# SensorTile_CR2032_V01.net
KiCad netlist of a schematic drawn in EAGLE
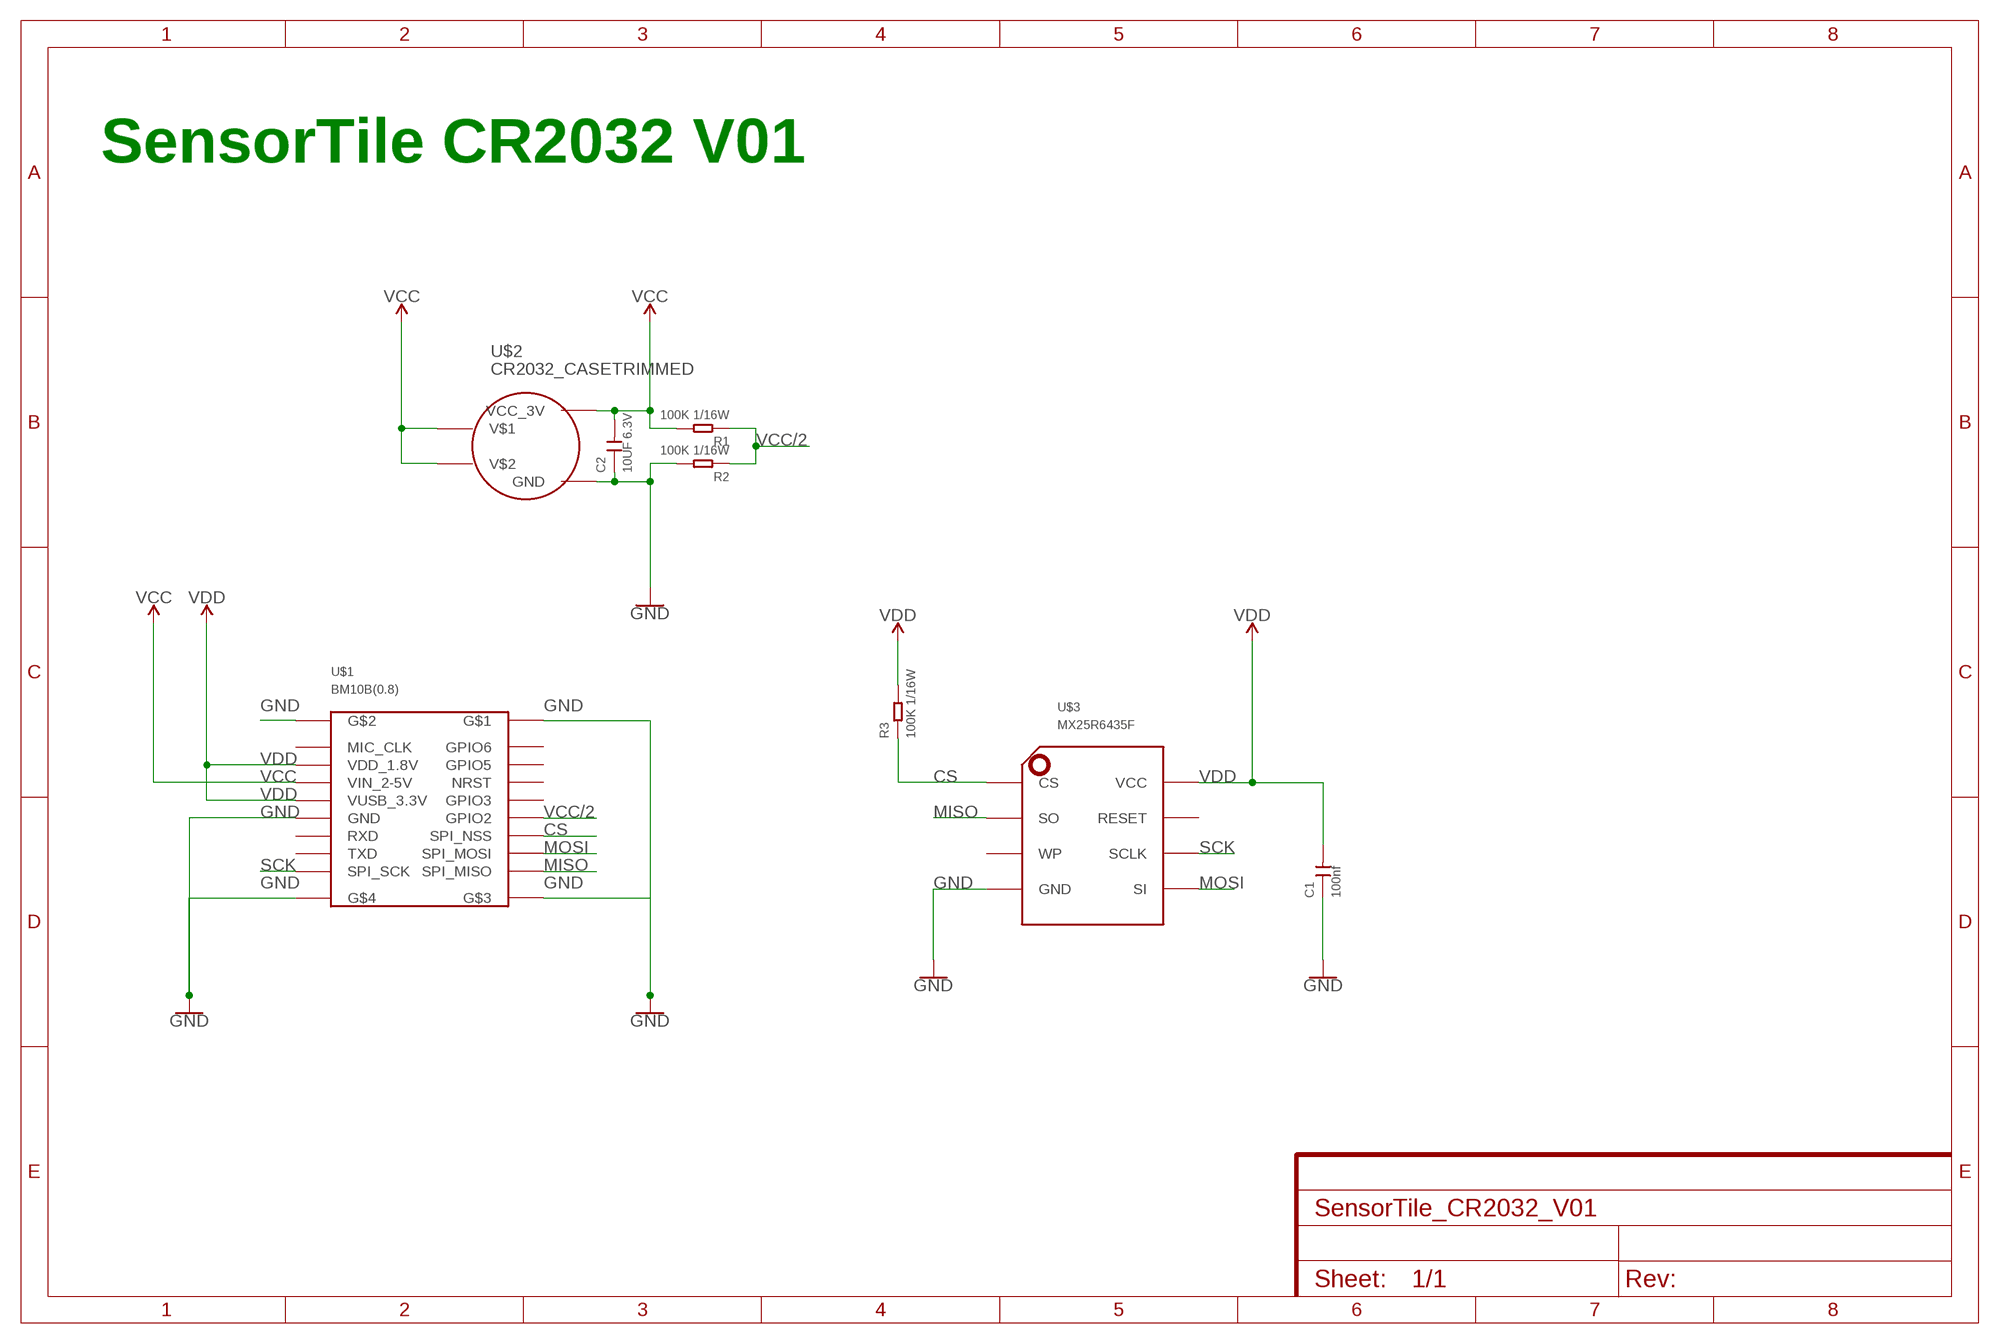
[diagram p0: schematic, sheet 1]

(export (version "E")
  (design (tool "Eeschema 10.0.6"))
  (components
    (comp (ref "C1")
      (value "100nf")
      (footprint "eagle-import:C0402")
      (fields (field (name "MPN") "CC0402KRX7R8BB104"))
      (libsource (lib "eagle-import") (part "CERAMIC-100NF-25V-10%-X7R(0402)"))
    )
    (comp (ref "C2")
      (value "10UF 6.3V")
      (footprint "eagle-import:C0603")
      (fields (field (name "MPN") "CC0603MRX5R5BB106"))
      (libsource (lib "eagle-import") (part "CERAMIC-10UF-6.3V-20%-X5R(0603)"))
    )
    (comp (ref "R1")
      (value "100K 1/16W")
      (footprint "eagle-import:R0402")
      (fields (field (name "MPN") "RC0402JR-07100KL"))
      (libsource (lib "eagle-import") (part "SMD-RES-100K-5%-1/16W(0402)"))
    )
    (comp (ref "R2")
      (value "100K 1/16W")
      (footprint "eagle-import:R0402")
      (fields (field (name "MPN") "RC0402JR-07100KL"))
      (libsource (lib "eagle-import") (part "SMD-RES-100K-5%-1/16W(0402)"))
    )
    (comp (ref "R3")
      (value "100K 1/16W")
      (footprint "eagle-import:R0402")
      (fields (field (name "MPN") "RC0402FR-0710KL"))
      (libsource (lib "eagle-import") (part "SMD-RES-10K-1%-1/16W(0402)"))
    )
    (comp (ref "U$1")
      (value "BM10B(0.8)")
      (footprint "eagle-import:BM10B(0.8)-16DP-0.4V(51)")
      (libsource (lib "eagle-import") (part "BM10B(0.8)-16DP-0.4V(51)"))
    )
    (comp (ref "U$2")
      (value "CR2032_CASETRIMMED")
      (footprint "eagle-import:CR2032_CASE_TRIMMED")
      (libsource (lib "eagle-import") (part "CR2032_CASETRIMMED"))
    )
    (comp (ref "U$3")
      (value "MX25R6435F")
      (footprint "eagle-import:8-USON_MX25R6435F")
      (libsource (lib "eagle-import") (part "MX25R6435F"))
    )
  )
  (nets
    (net (code "1") (name "/CS") (class "Default")
      (node (ref "R3") (pin "1") (pinfunction "1_1") (pintype "passive"))
      (node (ref "U$1") (pin "SPI_NSS") (pinfunction "SPI_NSS_SPI_NSS") (pintype "bidirectional"))
      (node (ref "U$3") (pin "CS$1") (pinfunction "CS_CS$1") (pintype "bidirectional"))
    )
    (net (code "2") (name "/MISO") (class "Default")
      (node (ref "U$1") (pin "SPI_MISO") (pinfunction "SPI_MISO_SPI_MISO") (pintype "bidirectional"))
      (node (ref "U$3") (pin "SO$2") (pinfunction "SO_SO$2") (pintype "bidirectional"))
    )
    (net (code "3") (name "/MOSI") (class "Default")
      (node (ref "U$1") (pin "SPI_MOSI") (pinfunction "SPI_MOSI_SPI_MOSI") (pintype "bidirectional"))
      (node (ref "U$3") (pin "SI$5") (pinfunction "SI_SI$5") (pintype "bidirectional"))
    )
    (net (code "4") (name "/SCK") (class "Default")
      (node (ref "U$1") (pin "SPI_SCK") (pinfunction "SPI_SCK_SPI_SCK") (pintype "bidirectional"))
      (node (ref "U$3") (pin "SCLK$6") (pinfunction "SCLK_SCLK$6") (pintype "bidirectional"))
    )
    (net (code "5") (name "/VCC{slash}2") (class "Default")
      (node (ref "R1") (pin "1") (pinfunction "1_1") (pintype "passive"))
      (node (ref "R2") (pin "1") (pinfunction "1_1") (pintype "passive"))
      (node (ref "U$1") (pin "GPIO2") (pinfunction "GPIO2_GPIO2") (pintype "bidirectional"))
    )
    (net (code "6") (name "GND") (class "Default")
      (node (ref "C1") (pin "1") (pinfunction "1_1") (pintype "passive"))
      (node (ref "C2") (pin "1") (pinfunction "1_1") (pintype "passive"))
      (node (ref "R2") (pin "2") (pinfunction "2_2") (pintype "passive"))
      (node (ref "U$1") (pin "G$1") (pinfunction "G$1_G$1") (pintype "bidirectional"))
      (node (ref "U$1") (pin "G$2") (pinfunction "G$2_G$2") (pintype "bidirectional"))
      (node (ref "U$1") (pin "G$3") (pinfunction "G$3_G$3") (pintype "bidirectional"))
      (node (ref "U$1") (pin "G$4") (pinfunction "G$4_G$4") (pintype "bidirectional"))
      (node (ref "U$1") (pin "GND$1") (pinfunction "GND_GND$1") (pintype "bidirectional"))
      (node (ref "U$2") (pin "GND") (pinfunction "GND_GND") (pintype "bidirectional"))
      (node (ref "U$3") (pin "GND$4") (pinfunction "GND_GND$4") (pintype "bidirectional"))
    )
    (net (code "7") (name "VCC") (class "Default")
      (node (ref "C2") (pin "2") (pinfunction "2_2") (pintype "passive"))
      (node (ref "R1") (pin "2") (pinfunction "2_2") (pintype "passive"))
      (node (ref "U$1") (pin "VIN_2-5V") (pinfunction "VIN_2-5V_VIN_2-5V") (pintype "bidirectional"))
      (node (ref "U$2") (pin "VCC@1") (pinfunction "V$1_VCC@1") (pintype "bidirectional"))
      (node (ref "U$2") (pin "VCC@2") (pinfunction "V$2_VCC@2") (pintype "bidirectional"))
      (node (ref "U$2") (pin "VCC_3V") (pinfunction "VCC_3V_VCC_3V") (pintype "bidirectional"))
    )
    (net (code "8") (name "VDD") (class "Default")
      (node (ref "C1") (pin "2") (pinfunction "2_2") (pintype "passive"))
      (node (ref "R3") (pin "2") (pinfunction "2_2") (pintype "passive"))
      (node (ref "U$1") (pin "VDD_1.8V") (pinfunction "VDD_1.8V_VDD_1.8V") (pintype "bidirectional"))
      (node (ref "U$1") (pin "VUSB_3.3V") (pinfunction "VUSB_3.3V_VUSB_3.3V") (pintype "bidirectional"))
      (node (ref "U$3") (pin "VCC$8") (pinfunction "VCC_VCC$8") (pintype "bidirectional"))
    )
    (net (code "9") (name "unconnected-(U$1-PadGPIO3)") (class "Default")
      (node (ref "U$1") (pin "GPIO3") (pinfunction "GPIO3_GPIO3") (pintype "bidirectional"))
    )
    (net (code "10") (name "unconnected-(U$1-PadGPIO5)") (class "Default")
      (node (ref "U$1") (pin "GPIO5") (pinfunction "GPIO5_GPIO5") (pintype "bidirectional"))
    )
    (net (code "11") (name "unconnected-(U$1-PadGPIO6)") (class "Default")
      (node (ref "U$1") (pin "GPIO6") (pinfunction "GPIO6_GPIO6") (pintype "bidirectional"))
    )
    (net (code "12") (name "unconnected-(U$1-PadMIC_CLK)") (class "Default")
      (node (ref "U$1") (pin "MIC_CLK") (pinfunction "MIC_CLK_MIC_CLK") (pintype "bidirectional"))
    )
    (net (code "13") (name "unconnected-(U$1-PadNRST)") (class "Default")
      (node (ref "U$1") (pin "NRST") (pinfunction "NRST_NRST") (pintype "bidirectional"))
    )
    (net (code "14") (name "unconnected-(U$1-PadRXD)") (class "Default")
      (node (ref "U$1") (pin "RXD") (pinfunction "RXD_RXD") (pintype "bidirectional"))
    )
    (net (code "15") (name "unconnected-(U$1-PadTXD)") (class "Default")
      (node (ref "U$1") (pin "TXD") (pinfunction "TXD_TXD") (pintype "bidirectional"))
    )
    (net (code "16") (name "unconnected-(U$3-RESET-PadRESET$7)") (class "Default")
      (node (ref "U$3") (pin "RESET$7") (pinfunction "RESET_RESET$7") (pintype "bidirectional"))
    )
    (net (code "17") (name "unconnected-(U$3-WP-PadWP$3)") (class "Default")
      (node (ref "U$3") (pin "WP$3") (pinfunction "WP_WP$3") (pintype "bidirectional"))
    )
  )
)
